# Push-It-V1_0.net
KiCad netlist of a schematic drawn in EAGLE
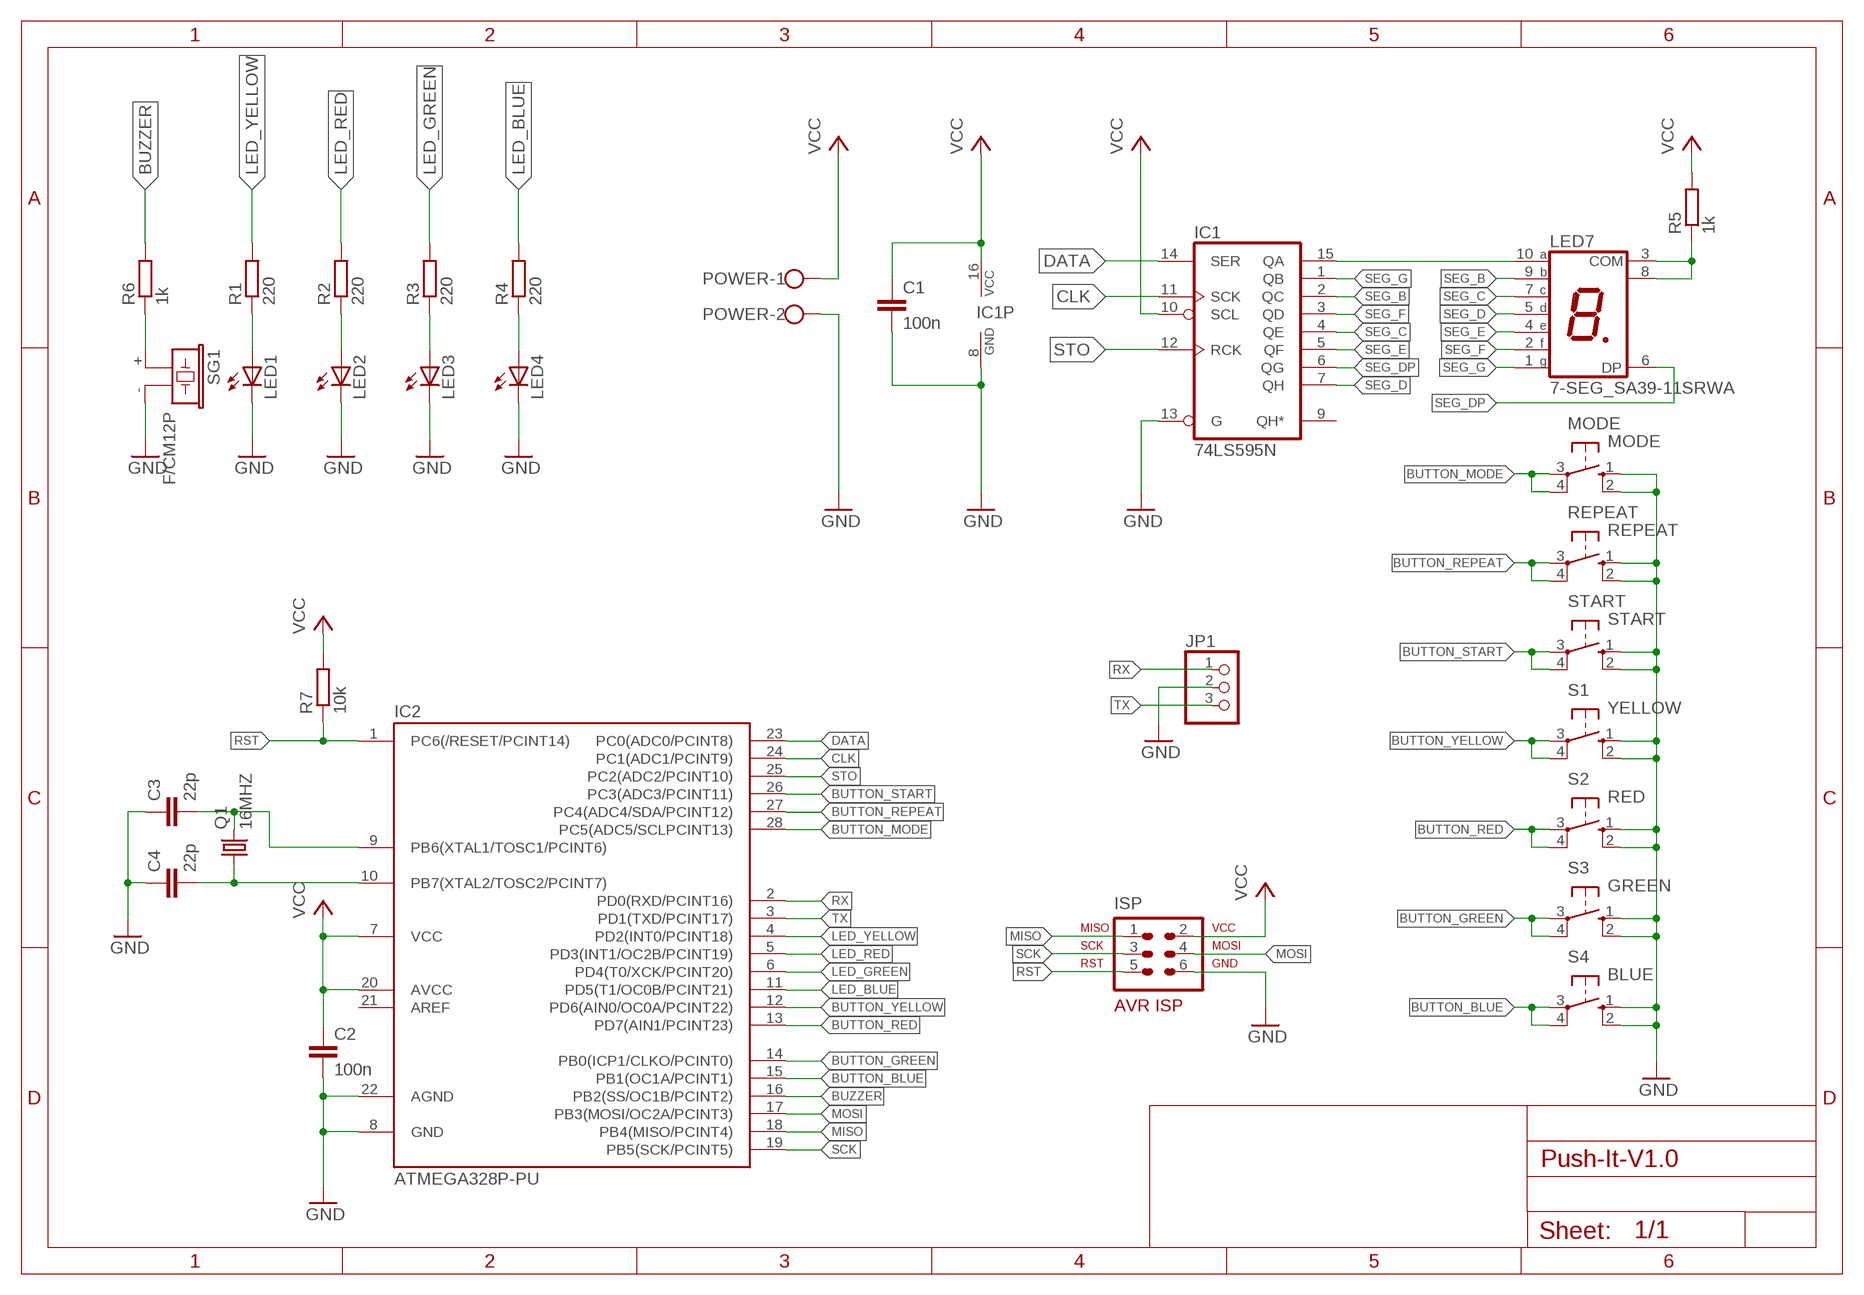
[diagram p0: schematic, sheet 1]

(export (version "E")
  (design (tool "Eeschema 10.0.6"))
  (components
    (comp (ref "C1")
      (value "100n")
      (footprint "eagle-import:C025-025X050")
      (libsource (lib "eagle-import") (part "C-EU025-025X050"))
    )
    (comp (ref "C2")
      (value "100n")
      (footprint "eagle-import:C025-025X050")
      (libsource (lib "eagle-import") (part "C-EU025-025X050"))
    )
    (comp (ref "C3")
      (value "22p")
      (footprint "eagle-import:C025-025X050")
      (libsource (lib "eagle-import") (part "C-EU025-025X050"))
    )
    (comp (ref "C4")
      (value "22p")
      (footprint "eagle-import:C025-025X050")
      (libsource (lib "eagle-import") (part "C-EU025-025X050"))
    )
    (comp (ref "IC1")
      (value "74LS595N")
      (footprint "eagle-import:DIL16")
      (libsource (lib "eagle-import") (part "74595NLS"))
    )
    (comp (ref "IC2")
      (value "ATMEGA328P-PU")
      (footprint "eagle-import:DIL28-3")
      (libsource (lib "eagle-import") (part "MEGA48/88/168-PU"))
    )
    (comp (ref "ISP")
      (value "AVR-ISP-6VERT")
      (footprint "eagle-import:AVR-ISP-6")
      (libsource (lib "eagle-import") (part "AVR-ISP-6VERT"))
    )
    (comp (ref "JP1")
      (value "PINHD-1X3/90")
      (footprint "eagle-import:1X03_90")
      (libsource (lib "eagle-import") (part "PINHD-1X3/90"))
    )
    (comp (ref "LED1")
      (value "LED10MM")
      (footprint "eagle-import:LED10MM")
      (libsource (lib "eagle-import") (part "LED10MM"))
    )
    (comp (ref "LED2")
      (value "LED10MM")
      (footprint "eagle-import:LED10MM")
      (libsource (lib "eagle-import") (part "LED10MM"))
    )
    (comp (ref "LED3")
      (value "LED10MM")
      (footprint "eagle-import:LED10MM")
      (libsource (lib "eagle-import") (part "LED10MM"))
    )
    (comp (ref "LED4")
      (value "LED10MM")
      (footprint "eagle-import:LED10MM")
      (libsource (lib "eagle-import") (part "LED10MM"))
    )
    (comp (ref "LED7")
      (value "7-SEG_SA39-11SRWA")
      (footprint "eagle-import:SA39-11SRWA")
      (libsource (lib "eagle-import") (part "7-SEG_SA39-11SRWA"))
    )
    (comp (ref "MODE")
      (value "MODE")
      (footprint "eagle-import:B3F-10XX")
      (fields (field (name "MPN") "B3F-1000"))
      (libsource (lib "eagle-import") (part "10-XX"))
    )
    (comp (ref "POWER")
      (value "W237-102")
      (footprint "eagle-import:W237-102")
      (fields (field (name "MPN") "237-102"))
      (libsource (lib "eagle-import") (part "W237-102"))
    )
    (comp (ref "Q1")
      (value "16MHZ")
      (footprint "eagle-import:HC49_S")
      (libsource (lib "eagle-import") (part "CRYSTALHC49S"))
    )
    (comp (ref "R1")
      (value "220")
      (footprint "eagle-import:0207_7")
      (libsource (lib "eagle-import") (part "R-EU_0207/7"))
    )
    (comp (ref "R2")
      (value "220")
      (footprint "eagle-import:0207_7")
      (libsource (lib "eagle-import") (part "R-EU_0207/7"))
    )
    (comp (ref "R3")
      (value "220")
      (footprint "eagle-import:0207_7")
      (libsource (lib "eagle-import") (part "R-EU_0207/7"))
    )
    (comp (ref "R4")
      (value "220")
      (footprint "eagle-import:0207_7")
      (libsource (lib "eagle-import") (part "R-EU_0207/7"))
    )
    (comp (ref "R5")
      (value "1k")
      (footprint "eagle-import:0207_7")
      (libsource (lib "eagle-import") (part "R-EU_0207/7"))
    )
    (comp (ref "R6")
      (value "1k")
      (footprint "eagle-import:0207_7")
      (libsource (lib "eagle-import") (part "R-EU_0207/7"))
    )
    (comp (ref "R7")
      (value "10k")
      (footprint "eagle-import:0207_7")
      (libsource (lib "eagle-import") (part "R-EU_0207/7"))
    )
    (comp (ref "REPEAT")
      (value "REPEAT")
      (footprint "eagle-import:B3F-10XX")
      (fields (field (name "MPN") "B3F-1000"))
      (libsource (lib "eagle-import") (part "10-XX"))
    )
    (comp (ref "S1")
      (value "YELLOW")
      (footprint "eagle-import:B3F-10XX")
      (fields (field (name "MPN") "B3F-1000"))
      (libsource (lib "eagle-import") (part "10-XX"))
    )
    (comp (ref "S2")
      (value "RED")
      (footprint "eagle-import:B3F-10XX")
      (fields (field (name "MPN") "B3F-1000"))
      (libsource (lib "eagle-import") (part "10-XX"))
    )
    (comp (ref "S3")
      (value "GREEN")
      (footprint "eagle-import:B3F-10XX")
      (fields (field (name "MPN") "B3F-1000"))
      (libsource (lib "eagle-import") (part "10-XX"))
    )
    (comp (ref "S4")
      (value "BLUE")
      (footprint "eagle-import:B3F-10XX")
      (fields (field (name "MPN") "B3F-1000"))
      (libsource (lib "eagle-import") (part "10-XX"))
    )
    (comp (ref "SG1")
      (value "F/CM12P")
      (footprint "eagle-import:F_CM12P")
      (libsource (lib "eagle-import") (part "F/CM12P"))
    )
    (comp (ref "START")
      (value "START")
      (footprint "eagle-import:B3F-10XX")
      (fields (field (name "MPN") "B3F-1000"))
      (libsource (lib "eagle-import") (part "10-XX"))
    )
  )
  (nets
    (net (code "1") (name "BUTTON_BLUE") (class "Default")
      (node (ref "IC2") (pin "15") (pinfunction "PB1(OC1A/PCINT1)_15") (pintype "bidirectional"))
      (node (ref "S4") (pin "3") (pinfunction "P_3") (pintype "passive"))
      (node (ref "S4") (pin "4") (pinfunction "P1_4") (pintype "passive"))
    )
    (net (code "2") (name "BUTTON_GREEN") (class "Default")
      (node (ref "IC2") (pin "14") (pinfunction "PB0(ICP1/CLKO/PCINT0)_14") (pintype "bidirectional"))
      (node (ref "S3") (pin "3") (pinfunction "P_3") (pintype "passive"))
      (node (ref "S3") (pin "4") (pinfunction "P1_4") (pintype "passive"))
    )
    (net (code "3") (name "BUTTON_MODE") (class "Default")
      (node (ref "IC2") (pin "28") (pinfunction "PC5(ADC5/SCLPCINT13)_28") (pintype "bidirectional"))
      (node (ref "MODE") (pin "3") (pinfunction "P_3") (pintype "passive"))
      (node (ref "MODE") (pin "4") (pinfunction "P1_4") (pintype "passive"))
    )
    (net (code "4") (name "BUTTON_RED") (class "Default")
      (node (ref "IC2") (pin "13") (pinfunction "PD7(AIN1/PCINT23)_13") (pintype "bidirectional"))
      (node (ref "S2") (pin "3") (pinfunction "P_3") (pintype "passive"))
      (node (ref "S2") (pin "4") (pinfunction "P1_4") (pintype "passive"))
    )
    (net (code "5") (name "BUTTON_REPEAT") (class "Default")
      (node (ref "IC2") (pin "27") (pinfunction "PC4(ADC4/SDA/PCINT12)_27") (pintype "bidirectional"))
      (node (ref "REPEAT") (pin "3") (pinfunction "P_3") (pintype "passive"))
      (node (ref "REPEAT") (pin "4") (pinfunction "P1_4") (pintype "passive"))
    )
    (net (code "6") (name "BUTTON_START") (class "Default")
      (node (ref "IC2") (pin "26") (pinfunction "PC3(ADC3/PCINT11)_26") (pintype "bidirectional"))
      (node (ref "START") (pin "3") (pinfunction "P_3") (pintype "passive"))
      (node (ref "START") (pin "4") (pinfunction "P1_4") (pintype "passive"))
    )
    (net (code "7") (name "BUTTON_YELLOW") (class "Default")
      (node (ref "IC2") (pin "12") (pinfunction "PD6(AIN0/OC0A/PCINT22)_12") (pintype "bidirectional"))
      (node (ref "S1") (pin "3") (pinfunction "P_3") (pintype "passive"))
      (node (ref "S1") (pin "4") (pinfunction "P1_4") (pintype "passive"))
    )
    (net (code "8") (name "BUZZER") (class "Default")
      (node (ref "IC2") (pin "16") (pinfunction "PB2(SS/OC1B/PCINT2)_16") (pintype "bidirectional"))
      (node (ref "R6") (pin "2") (pinfunction "2_2") (pintype "passive"))
    )
    (net (code "9") (name "CLK") (class "Default")
      (node (ref "IC1") (pin "11") (pinfunction "SCK_11") (pintype "input"))
      (node (ref "IC2") (pin "24") (pinfunction "PC1(ADC1/PCINT9)_24") (pintype "bidirectional"))
    )
    (net (code "10") (name "DATA") (class "Default")
      (node (ref "IC1") (pin "14") (pinfunction "SER_14") (pintype "input"))
      (node (ref "IC2") (pin "23") (pinfunction "PC0(ADC0/PCINT8)_23") (pintype "bidirectional"))
    )
    (net (code "11") (name "GND") (class "Default")
      (node (ref "C1") (pin "2") (pinfunction "2_2") (pintype "passive"))
      (node (ref "C2") (pin "2") (pinfunction "2_2") (pintype "passive"))
      (node (ref "C3") (pin "1") (pinfunction "1_1") (pintype "passive"))
      (node (ref "C4") (pin "1") (pinfunction "1_1") (pintype "passive"))
      (node (ref "IC1") (pin "13") (pinfunction "G_13") (pintype "input"))
      (node (ref "IC1") (pin "8") (pinfunction "GND_8") (pintype "power_in"))
      (node (ref "IC2") (pin "22") (pinfunction "AGND_22") (pintype "power_in"))
      (node (ref "IC2") (pin "8") (pinfunction "GND_8") (pintype "power_in"))
      (node (ref "ISP") (pin "6") (pinfunction "6_6") (pintype "passive"))
      (node (ref "JP1") (pin "2") (pinfunction "2_2") (pintype "passive"))
      (node (ref "LED1") (pin "K") (pinfunction "C_K") (pintype "passive"))
      (node (ref "LED2") (pin "K") (pinfunction "C_K") (pintype "passive"))
      (node (ref "LED3") (pin "K") (pinfunction "C_K") (pintype "passive"))
      (node (ref "LED4") (pin "K") (pinfunction "C_K") (pintype "passive"))
      (node (ref "MODE") (pin "1") (pinfunction "S_1") (pintype "passive"))
      (node (ref "MODE") (pin "2") (pinfunction "S1_2") (pintype "passive"))
      (node (ref "POWER") (pin "2") (pinfunction "KL_2") (pintype "passive"))
      (node (ref "REPEAT") (pin "1") (pinfunction "S_1") (pintype "passive"))
      (node (ref "REPEAT") (pin "2") (pinfunction "S1_2") (pintype "passive"))
      (node (ref "S1") (pin "1") (pinfunction "S_1") (pintype "passive"))
      (node (ref "S1") (pin "2") (pinfunction "S1_2") (pintype "passive"))
      (node (ref "S2") (pin "1") (pinfunction "S_1") (pintype "passive"))
      (node (ref "S2") (pin "2") (pinfunction "S1_2") (pintype "passive"))
      (node (ref "S3") (pin "1") (pinfunction "S_1") (pintype "passive"))
      (node (ref "S3") (pin "2") (pinfunction "S1_2") (pintype "passive"))
      (node (ref "S4") (pin "1") (pinfunction "S_1") (pintype "passive"))
      (node (ref "S4") (pin "2") (pinfunction "S1_2") (pintype "passive"))
      (node (ref "SG1") (pin "-") (pinfunction "2_-") (pintype "passive"))
      (node (ref "START") (pin "1") (pinfunction "S_1") (pintype "passive"))
      (node (ref "START") (pin "2") (pinfunction "S1_2") (pintype "passive"))
    )
    (net (code "12") (name "LED_BLUE") (class "Default")
      (node (ref "IC2") (pin "11") (pinfunction "PD5(T1/OC0B/PCINT21)_11") (pintype "bidirectional"))
      (node (ref "R4") (pin "2") (pinfunction "2_2") (pintype "passive"))
    )
    (net (code "13") (name "LED_GREEN") (class "Default")
      (node (ref "IC2") (pin "6") (pinfunction "PD4(T0/XCK/PCINT20)_6") (pintype "bidirectional"))
      (node (ref "R3") (pin "2") (pinfunction "2_2") (pintype "passive"))
    )
    (net (code "14") (name "LED_RED") (class "Default")
      (node (ref "IC2") (pin "5") (pinfunction "PD3(INT1/OC2B/PCINT19)_5") (pintype "bidirectional"))
      (node (ref "R2") (pin "2") (pinfunction "2_2") (pintype "passive"))
    )
    (net (code "15") (name "LED_YELLOW") (class "Default")
      (node (ref "IC2") (pin "4") (pinfunction "PD2(INT0/PCINT18)_4") (pintype "bidirectional"))
      (node (ref "R1") (pin "2") (pinfunction "2_2") (pintype "passive"))
    )
    (net (code "16") (name "MISO") (class "Default")
      (node (ref "IC2") (pin "18") (pinfunction "PB4(MISO/PCINT4)_18") (pintype "bidirectional"))
      (node (ref "ISP") (pin "1") (pinfunction "1_1") (pintype "passive"))
    )
    (net (code "17") (name "MOSI") (class "Default")
      (node (ref "IC2") (pin "17") (pinfunction "PB3(MOSI/OC2A/PCINT3)_17") (pintype "bidirectional"))
      (node (ref "ISP") (pin "4") (pinfunction "4_4") (pintype "passive"))
    )
    (net (code "18") (name "Net-(IC1A-QA)") (class "Default")
      (node (ref "IC1") (pin "15") (pinfunction "QA_15") (pintype "tri_state"))
      (node (ref "LED7") (pin "10") (pinfunction "A_10") (pintype "passive"))
    )
    (net (code "19") (name "Net-(IC2-PB6(XTAL1{slash}TOSC1{slash}PCINT6))") (class "Default")
      (node (ref "C3") (pin "2") (pinfunction "2_2") (pintype "passive"))
      (node (ref "IC2") (pin "9") (pinfunction "PB6(XTAL1/TOSC1/PCINT6)_9") (pintype "bidirectional"))
      (node (ref "Q1") (pin "2") (pinfunction "2_2") (pintype "passive"))
    )
    (net (code "20") (name "Net-(IC2-PB7(XTAL2{slash}TOSC2{slash}PCINT7))") (class "Default")
      (node (ref "C4") (pin "2") (pinfunction "2_2") (pintype "passive"))
      (node (ref "IC2") (pin "10") (pinfunction "PB7(XTAL2/TOSC2/PCINT7)_10") (pintype "bidirectional"))
      (node (ref "Q1") (pin "1") (pinfunction "1_1") (pintype "passive"))
    )
    (net (code "21") (name "Net-(LED1-PadA)") (class "Default")
      (node (ref "LED1") (pin "A") (pinfunction "A_A") (pintype "passive"))
      (node (ref "R1") (pin "1") (pinfunction "1_1") (pintype "passive"))
    )
    (net (code "22") (name "Net-(LED2-PadA)") (class "Default")
      (node (ref "LED2") (pin "A") (pinfunction "A_A") (pintype "passive"))
      (node (ref "R2") (pin "1") (pinfunction "1_1") (pintype "passive"))
    )
    (net (code "23") (name "Net-(LED3-PadA)") (class "Default")
      (node (ref "LED3") (pin "A") (pinfunction "A_A") (pintype "passive"))
      (node (ref "R3") (pin "1") (pinfunction "1_1") (pintype "passive"))
    )
    (net (code "24") (name "Net-(LED4-PadA)") (class "Default")
      (node (ref "LED4") (pin "A") (pinfunction "A_A") (pintype "passive"))
      (node (ref "R4") (pin "1") (pinfunction "1_1") (pintype "passive"))
    )
    (net (code "25") (name "Net-(LED7-COM-Pad3)") (class "Default")
      (node (ref "LED7") (pin "3") (pinfunction "COM_3") (pintype "passive"))
      (node (ref "LED7") (pin "8") (pinfunction "COM_8") (pintype "passive"))
      (node (ref "R5") (pin "1") (pinfunction "1_1") (pintype "passive"))
    )
    (net (code "26") (name "Net-(SG1-1)") (class "Default")
      (node (ref "R6") (pin "1") (pinfunction "1_1") (pintype "passive"))
      (node (ref "SG1") (pin "+") (pinfunction "1_+") (pintype "passive"))
    )
    (net (code "27") (name "RST") (class "Default")
      (node (ref "IC2") (pin "1") (pinfunction "PC6(/RESET/PCINT14)_1") (pintype "bidirectional"))
      (node (ref "ISP") (pin "5") (pinfunction "5_5") (pintype "passive"))
      (node (ref "R7") (pin "1") (pinfunction "1_1") (pintype "passive"))
    )
    (net (code "28") (name "RX") (class "Default")
      (node (ref "IC2") (pin "2") (pinfunction "PD0(RXD/PCINT16)_2") (pintype "bidirectional"))
      (node (ref "JP1") (pin "1") (pinfunction "1_1") (pintype "passive"))
    )
    (net (code "29") (name "SCK") (class "Default")
      (node (ref "IC2") (pin "19") (pinfunction "PB5(SCK/PCINT5)_19") (pintype "bidirectional"))
      (node (ref "ISP") (pin "3") (pinfunction "3_3") (pintype "passive"))
    )
    (net (code "30") (name "SEG_B") (class "Default")
      (node (ref "IC1") (pin "2") (pinfunction "QC_2") (pintype "tri_state"))
      (node (ref "LED7") (pin "9") (pinfunction "B_9") (pintype "passive"))
    )
    (net (code "31") (name "SEG_C") (class "Default")
      (node (ref "IC1") (pin "4") (pinfunction "QE_4") (pintype "tri_state"))
      (node (ref "LED7") (pin "7") (pinfunction "C_7") (pintype "passive"))
    )
    (net (code "32") (name "SEG_D") (class "Default")
      (node (ref "IC1") (pin "7") (pinfunction "QH_7") (pintype "tri_state"))
      (node (ref "LED7") (pin "5") (pinfunction "D_5") (pintype "passive"))
    )
    (net (code "33") (name "SEG_DP") (class "Default")
      (node (ref "IC1") (pin "6") (pinfunction "QG_6") (pintype "tri_state"))
      (node (ref "LED7") (pin "6") (pinfunction "DP_6") (pintype "passive"))
    )
    (net (code "34") (name "SEG_E") (class "Default")
      (node (ref "IC1") (pin "5") (pinfunction "QF_5") (pintype "tri_state"))
      (node (ref "LED7") (pin "4") (pinfunction "E_4") (pintype "passive"))
    )
    (net (code "35") (name "SEG_F") (class "Default")
      (node (ref "IC1") (pin "3") (pinfunction "QD_3") (pintype "tri_state"))
      (node (ref "LED7") (pin "2") (pinfunction "F_2") (pintype "passive"))
    )
    (net (code "36") (name "SEG_G") (class "Default")
      (node (ref "IC1") (pin "1") (pinfunction "QB_1") (pintype "tri_state"))
      (node (ref "LED7") (pin "1") (pinfunction "G_1") (pintype "passive"))
    )
    (net (code "37") (name "STO") (class "Default")
      (node (ref "IC1") (pin "12") (pinfunction "RCK_12") (pintype "input"))
      (node (ref "IC2") (pin "25") (pinfunction "PC2(ADC2/PCINT10)_25") (pintype "bidirectional"))
    )
    (net (code "38") (name "TX") (class "Default")
      (node (ref "IC2") (pin "3") (pinfunction "PD1(TXD/PCINT17)_3") (pintype "bidirectional"))
      (node (ref "JP1") (pin "3") (pinfunction "3_3") (pintype "passive"))
    )
    (net (code "39") (name "VCC") (class "Default")
      (node (ref "C1") (pin "1") (pinfunction "1_1") (pintype "passive"))
      (node (ref "C2") (pin "1") (pinfunction "1_1") (pintype "passive"))
      (node (ref "IC1") (pin "10") (pinfunction "SCL_10") (pintype "input"))
      (node (ref "IC1") (pin "16") (pinfunction "VCC_16") (pintype "power_in"))
      (node (ref "IC2") (pin "20") (pinfunction "AVCC_20") (pintype "passive"))
      (node (ref "IC2") (pin "7") (pinfunction "VCC_7") (pintype "power_in"))
      (node (ref "ISP") (pin "2") (pinfunction "2_2") (pintype "passive"))
      (node (ref "POWER") (pin "1") (pinfunction "KL_1") (pintype "passive"))
      (node (ref "R5") (pin "2") (pinfunction "2_2") (pintype "passive"))
      (node (ref "R7") (pin "2") (pinfunction "2_2") (pintype "passive"))
    )
    (net (code "40") (name "unconnected-(IC1A-QH*-Pad9)") (class "Default")
      (node (ref "IC1") (pin "9") (pinfunction "QH*_9") (pintype "tri_state"))
    )
    (net (code "41") (name "unconnected-(IC2-AREF-Pad21)") (class "Default")
      (node (ref "IC2") (pin "21") (pinfunction "AREF_21") (pintype "passive"))
    )
  )
)
